# tx_no_transistor_adjustable_charging_cur.net
KiCad netlist of a schematic drawn in EAGLE
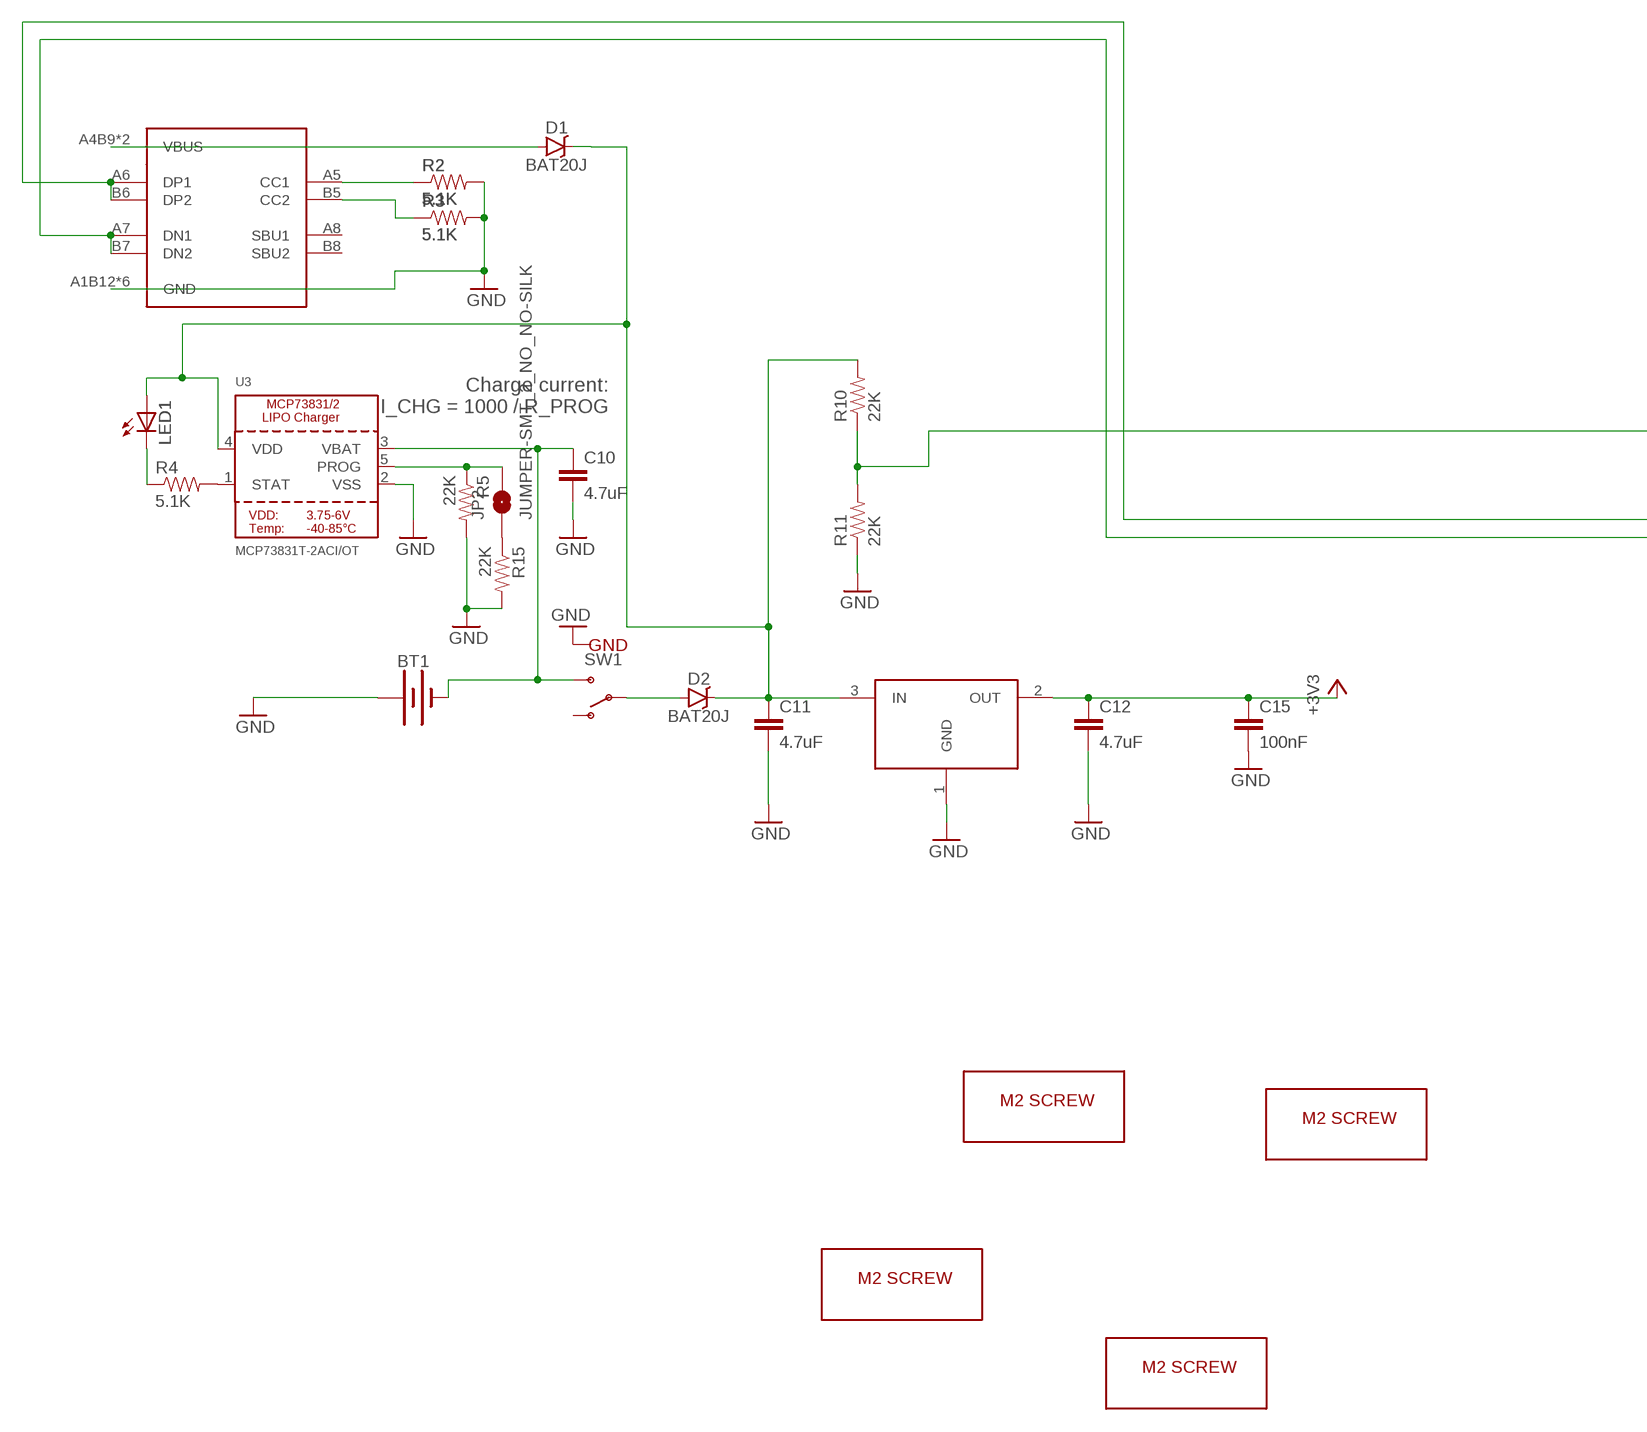
[diagram p0: schematic, sheet 1, part 1 of 2]
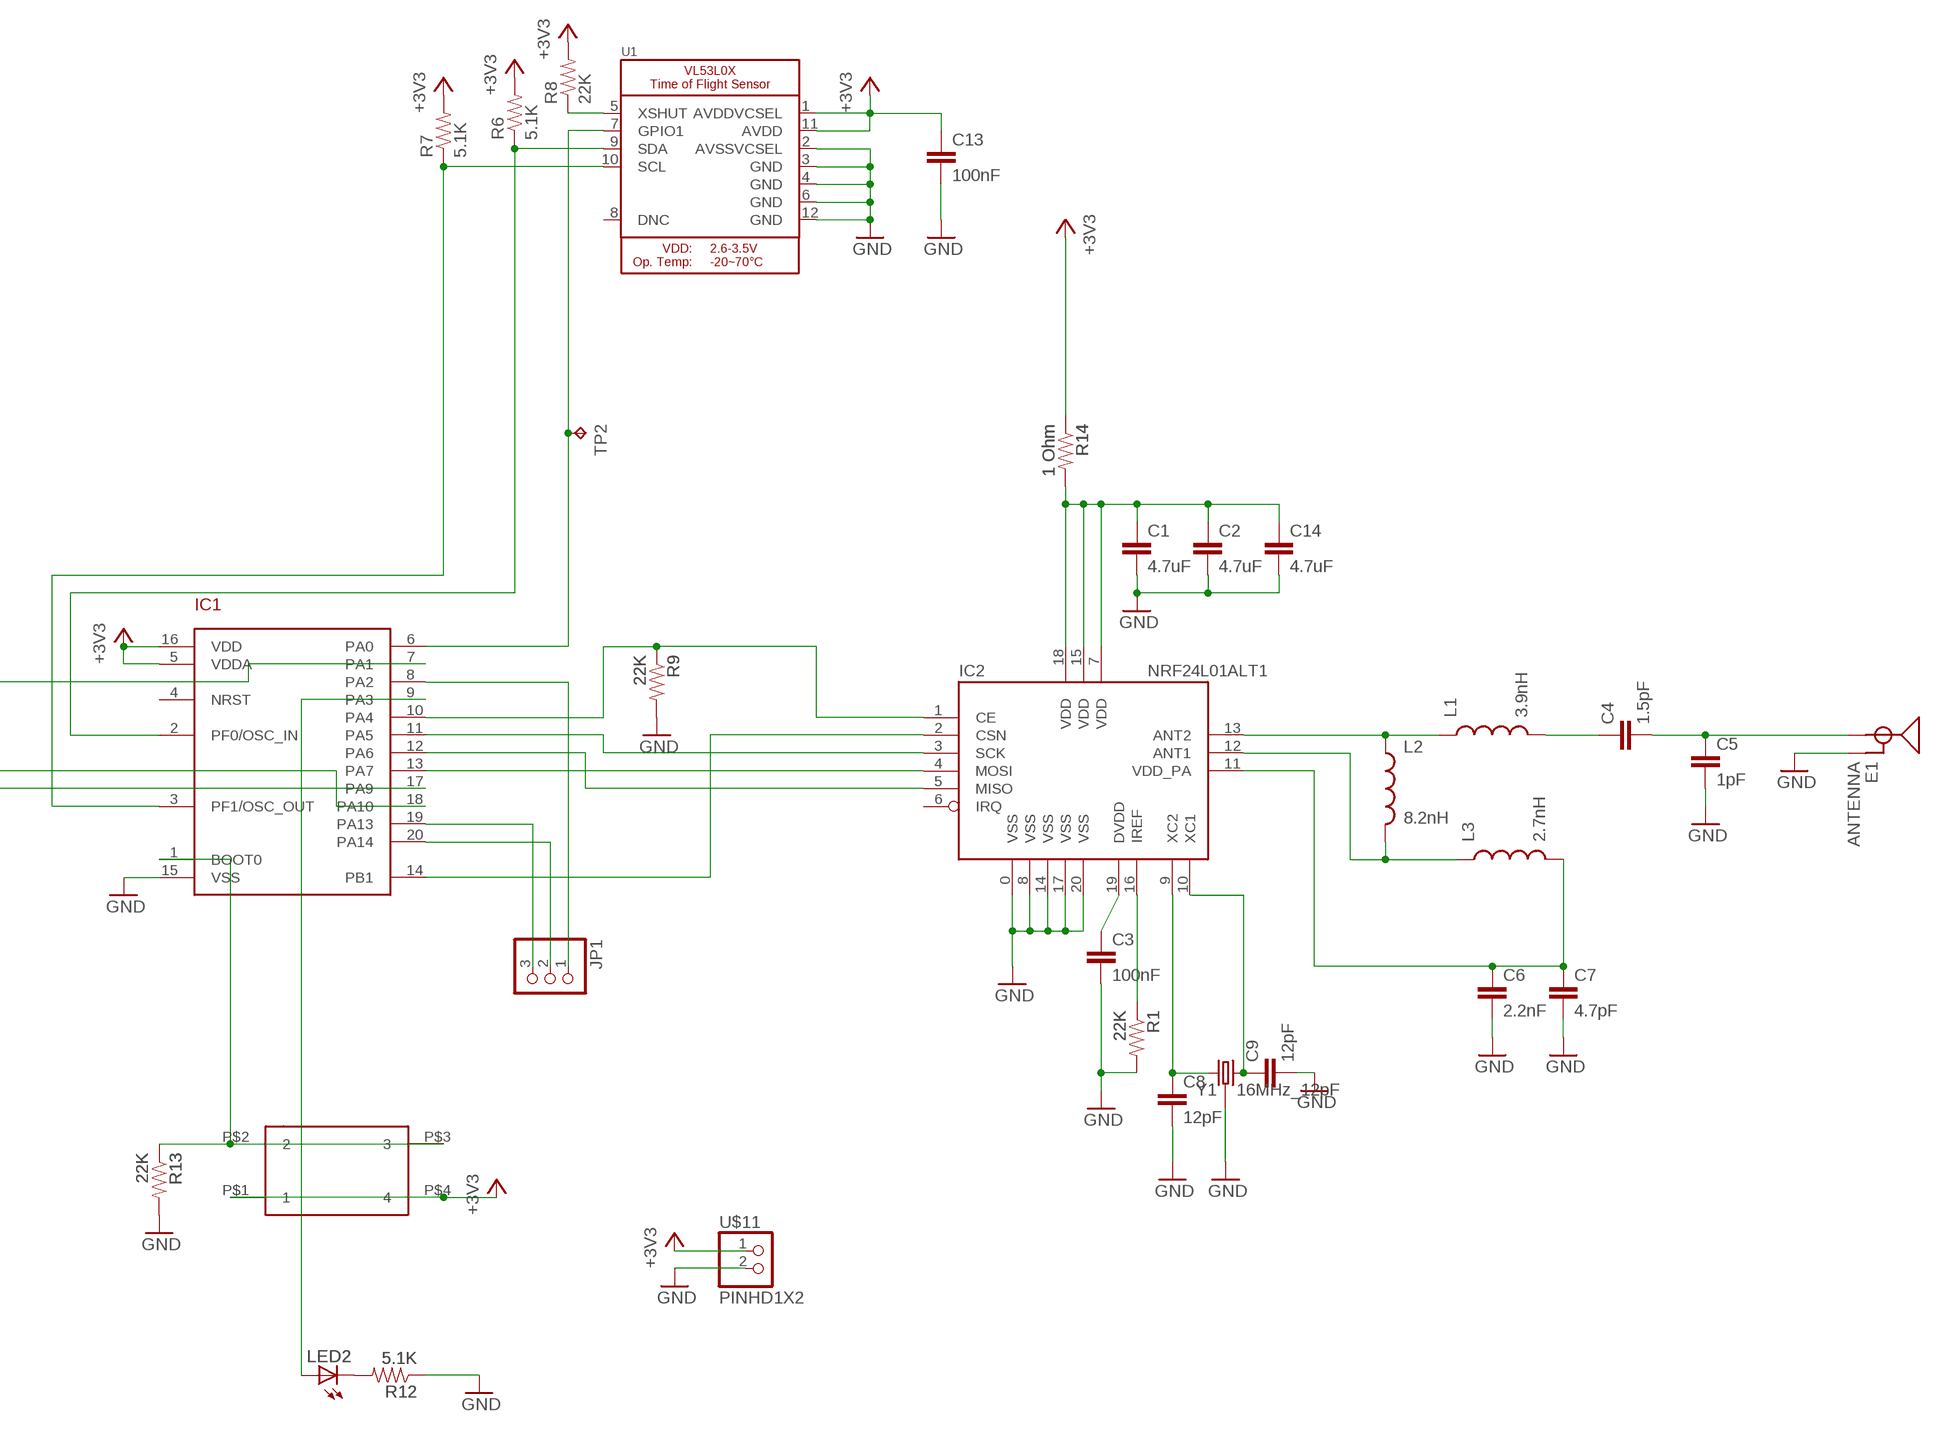
[diagram p1: schematic, sheet 1, part 2 of 2]

(export (version "E")
  (design (tool "Eeschema 10.0.6"))
  (components
    (comp (ref "BT1")
      (value "TX_SPARKFUN-BATTERIES_BATTERY-24.5MM_PTH")
      (footprint "eagle-import:TX_SPARKFUN-BATTERIES_BATTCON_24.5MM_PTH")
      (libsource (lib "eagle-import") (part "TX_SPARKFUN-BATTERIES_BATTERY-24.5MM_PTH"))
    )
    (comp (ref "C1")
      (value "4.7uF")
      (footprint "eagle-import:0805")
      (libsource (lib "eagle-import") (part "clock_CAP0805"))
    )
    (comp (ref "C2")
      (value "4.7uF")
      (footprint "eagle-import:0805")
      (libsource (lib "eagle-import") (part "clock_CAP0805"))
    )
    (comp (ref "C3")
      (value "100nF")
      (footprint "eagle-import:0805")
      (libsource (lib "eagle-import") (part "clock_CAP0805"))
    )
    (comp (ref "C4")
      (value "1.5pF")
      (footprint "eagle-import:0805")
      (libsource (lib "eagle-import") (part "clock_CAP0805"))
    )
    (comp (ref "C5")
      (value "1pF")
      (footprint "eagle-import:0805")
      (libsource (lib "eagle-import") (part "clock_CAP0805"))
    )
    (comp (ref "C6")
      (value "2.2nF")
      (footprint "eagle-import:0805")
      (libsource (lib "eagle-import") (part "clock_CAP0805"))
    )
    (comp (ref "C7")
      (value "4.7pF")
      (footprint "eagle-import:0805")
      (libsource (lib "eagle-import") (part "clock_CAP0805"))
    )
    (comp (ref "C8")
      (value "12pF")
      (footprint "eagle-import:0805")
      (libsource (lib "eagle-import") (part "clock_CAP0805"))
    )
    (comp (ref "C9")
      (value "12pF")
      (footprint "eagle-import:0805")
      (libsource (lib "eagle-import") (part "clock_CAP0805"))
    )
    (comp (ref "C10")
      (value "4.7uF")
      (footprint "eagle-import:0805")
      (libsource (lib "eagle-import") (part "CAP0805"))
    )
    (comp (ref "C11")
      (value "4.7uF")
      (footprint "eagle-import:0805")
      (libsource (lib "eagle-import") (part "clock_CAP0805"))
    )
    (comp (ref "C12")
      (value "4.7uF")
      (footprint "eagle-import:0805")
      (libsource (lib "eagle-import") (part "clock_CAP0805"))
    )
    (comp (ref "C13")
      (value "100nF")
      (footprint "eagle-import:0805")
      (libsource (lib "eagle-import") (part "clock_CAP0805"))
    )
    (comp (ref "C14")
      (value "4.7uF")
      (footprint "eagle-import:0805")
      (libsource (lib "eagle-import") (part "clock_CAP0805"))
    )
    (comp (ref "C15")
      (value "100nF")
      (footprint "eagle-import:0805")
      (libsource (lib "eagle-import") (part "clock_CAP0805"))
    )
    (comp (ref "D1")
      (value "BAT20J")
      (footprint "eagle-import:SOD-323")
      (libsource (lib "eagle-import") (part "DIODE-SCHOTTKY-BAT20J"))
    )
    (comp (ref "D2")
      (value "BAT20J")
      (footprint "eagle-import:SOD-323")
      (libsource (lib "eagle-import") (part "DIODE-SCHOTTKY-BAT20J"))
    )
    (comp (ref "E1")
      (value "ANTENNA")
      (footprint "eagle-import:TRACE_ANTENNA_2.4GHZ_25.7MM_TUNED")
      (libsource (lib "eagle-import") (part "ANTENNATRACE-TUNED"))
    )
    (comp (ref "IC1")
      (value "STM32F030F4")
      (footprint "eagle-import:TSSOP20")
      (libsource (lib "eagle-import") (part "STM32F030F4"))
    )
    (comp (ref "IC2")
      (value "NRF24L01ALT1")
      (footprint "eagle-import:QFN20_ALT1")
      (libsource (lib "eagle-import") (part "NRF24L01ALT1"))
    )
    (comp (ref "JP1")
      (value "PINHD-1X3CB")
      (footprint "eagle-import:1X03-CLEANBIG")
      (libsource (lib "eagle-import") (part "PINHD-1X3CB"))
    )
    (comp (ref "JP2")
      (value "JUMPER-SMT_2_NO_NO-SILK")
      (footprint "eagle-import:SMT-JUMPER_2_NO_NO-SILK")
      (libsource (lib "eagle-import") (part "JUMPER-SMT_2_NO_NO-SILK"))
    )
    (comp (ref "L1")
      (value "3.9nH")
      (footprint "eagle-import:0805")
      (libsource (lib "eagle-import") (part "INDUCTOR0805"))
    )
    (comp (ref "L2")
      (value "8.2nH")
      (footprint "eagle-import:0805")
      (libsource (lib "eagle-import") (part "INDUCTOR0805"))
    )
    (comp (ref "L3")
      (value "2.7nH")
      (footprint "eagle-import:0805")
      (libsource (lib "eagle-import") (part "INDUCTOR0805"))
    )
    (comp (ref "LED1")
      (value "LEDCHIP-LED0805")
      (footprint "eagle-import:CHIP-LED0805")
      (libsource (lib "eagle-import") (part "LEDCHIP-LED0805"))
    )
    (comp (ref "LED2")
      (value "LEDCHIP-LED0805")
      (footprint "eagle-import:CHIP-LED0805")
      (libsource (lib "eagle-import") (part "LEDCHIP-LED0805"))
    )
    (comp (ref "R1")
      (value "22K")
      (footprint "eagle-import:0805")
      (libsource (lib "eagle-import") (part "joyAnalog_RESISTOR0805-RES"))
    )
    (comp (ref "R2")
      (value "5.1K")
      (footprint "eagle-import:0805")
      (libsource (lib "eagle-import") (part "joyAnalog_RESISTOR0805-RES"))
    )
    (comp (ref "R3")
      (value "5.1K")
      (footprint "eagle-import:0805")
      (libsource (lib "eagle-import") (part "joyAnalog_RESISTOR0805-RES"))
    )
    (comp (ref "R4")
      (value "5.1K")
      (footprint "eagle-import:0805")
      (libsource (lib "eagle-import") (part "RESISTOR0805-RES"))
    )
    (comp (ref "R5")
      (value "22K")
      (footprint "eagle-import:0805")
      (libsource (lib "eagle-import") (part "RESISTOR0805-RES"))
    )
    (comp (ref "R6")
      (value "5.1K")
      (footprint "eagle-import:0805")
      (libsource (lib "eagle-import") (part "RESISTOR0805-RES"))
    )
    (comp (ref "R7")
      (value "5.1K")
      (footprint "eagle-import:0805")
      (libsource (lib "eagle-import") (part "RESISTOR0805-RES"))
    )
    (comp (ref "R8")
      (value "22K")
      (footprint "eagle-import:0805")
      (libsource (lib "eagle-import") (part "RESISTOR0805-RES"))
    )
    (comp (ref "R9")
      (value "22K")
      (footprint "eagle-import:0805")
      (libsource (lib "eagle-import") (part "joyAnalog_RESISTOR0805-RES"))
    )
    (comp (ref "R10")
      (value "22K")
      (footprint "eagle-import:0805")
      (libsource (lib "eagle-import") (part "RESISTOR0805-RES"))
    )
    (comp (ref "R11")
      (value "22K")
      (footprint "eagle-import:0805")
      (libsource (lib "eagle-import") (part "RESISTOR0805-RES"))
    )
    (comp (ref "R12")
      (value "5.1K")
      (footprint "eagle-import:0805")
      (libsource (lib "eagle-import") (part "joyAnalog_RESISTOR0805-RES"))
    )
    (comp (ref "R13")
      (value "22K")
      (footprint "eagle-import:0805")
      (libsource (lib "eagle-import") (part "joyAnalog_RESISTOR0805-RES"))
    )
    (comp (ref "R14")
      (value "1 Ohm")
      (footprint "eagle-import:0805")
      (libsource (lib "eagle-import") (part "joyAnalog_RESISTOR0805-RES"))
    )
    (comp (ref "R15")
      (value "22K")
      (footprint "eagle-import:0805")
      (libsource (lib "eagle-import") (part "RESISTOR0805-RES"))
    )
    (comp (ref "SW1")
      (value "SWITCH-SPDTTDFGDFG")
      (footprint "eagle-import:SWITCH-SPST-SMD-A")
      (libsource (lib "eagle-import") (part "SWITCH-SPDTTDFGDFG"))
    )
    (comp (ref "SW2")
      (value "324_SW324_SWITCH_FOOT_HOLE")
      (footprint "eagle-import:342_SWICH_FOOT_HOLE")
      (libsource (lib "eagle-import") (part "324_SW324_SWITCH_FOOT_HOLE"))
    )
    (comp (ref "TP2")
      (value "TPTP10R")
      (footprint "eagle-import:TP10R")
      (libsource (lib "eagle-import") (part "TPTP10R"))
    )
    (comp (ref "U$1")
      (value "M2_SCREW_DEV")
      (footprint "eagle-import:M2_SCREW_FOOT")
      (libsource (lib "eagle-import") (part "M2_SCREW_DEV"))
    )
    (comp (ref "U$11")
      (value "PINHD1X2")
      (footprint "eagle-import:1X02")
      (libsource (lib "eagle-import") (part "PINHD1X2"))
    )
    (comp (ref "U$12")
      (value "M2_SCREW_DEV")
      (footprint "eagle-import:M2_SCREW_FOOT")
      (libsource (lib "eagle-import") (part "M2_SCREW_DEV"))
    )
    (comp (ref "U$13")
      (value "M2_SCREW_DEV")
      (footprint "eagle-import:M2_SCREW_FOOT")
      (libsource (lib "eagle-import") (part "M2_SCREW_DEV"))
    )
    (comp (ref "U$14")
      (value "M2_SCREW_DEV")
      (footprint "eagle-import:M2_SCREW_FOOT")
      (libsource (lib "eagle-import") (part "M2_SCREW_DEV"))
    )
    (comp (ref "U1")
      (value "VL53L0X")
      (footprint "eagle-import:LGA12_ST")
      (libsource (lib "eagle-import") (part "VL53L0X"))
    )
    (comp (ref "U2")
      (value "USBC_16P")
      (footprint "eagle-import:USBC_16P_FOOT")
      (libsource (lib "eagle-import") (part "USBC_16P"))
    )
    (comp (ref "U3")
      (value "MCP73831T-2ACI/OT")
      (footprint "eagle-import:SOT23-5")
      (libsource (lib "eagle-import") (part "MCP73831/2"))
    )
    (comp (ref "U4")
      (value "XC6206_DEV")
      (footprint "eagle-import:SOT23R_INFINEON")
      (libsource (lib "eagle-import") (part "XC6206_DEV"))
    )
    (comp (ref "Y1")
      (value "16MHz_12pF")
      (footprint "eagle-import:CRYSTAL-SMD-3.2X2.5MM")
      (libsource (lib "eagle-import") (part "CRYSTAL-26MHZSMD-3.2X2.5"))
    )
  )
  (nets
    (net (code "1") (name "+3V3") (class "Default")
      (node (ref "C12") (pin "1") (pinfunction "1_1") (pintype "passive"))
      (node (ref "C13") (pin "1") (pinfunction "1_1") (pintype "passive"))
      (node (ref "C15") (pin "1") (pinfunction "1_1") (pintype "passive"))
      (node (ref "IC1") (pin "16") (pinfunction "VDD_16") (pintype "bidirectional"))
      (node (ref "IC1") (pin "5") (pinfunction "VDDA_5") (pintype "bidirectional"))
      (node (ref "R14") (pin "1") (pinfunction "1_1") (pintype "passive"))
      (node (ref "R6") (pin "2") (pinfunction "2_2") (pintype "passive"))
      (node (ref "R7") (pin "2") (pinfunction "2_2") (pintype "passive"))
      (node (ref "R8") (pin "2") (pinfunction "2_2") (pintype "passive"))
      (node (ref "SW2") (pin "P$1") (pinfunction "1_P$1") (pintype "bidirectional"))
      (node (ref "SW2") (pin "P$4") (pinfunction "4_P$4") (pintype "bidirectional"))
      (node (ref "U$11") (pin "1") (pinfunction "1_1") (pintype "passive"))
      (node (ref "U1") (pin "1") (pinfunction "AVDDVCSEL_1") (pintype "power_in"))
      (node (ref "U1") (pin "11") (pinfunction "AVDD_11") (pintype "power_in"))
      (node (ref "U4") (pin "2") (pinfunction "OUT_2") (pintype "bidirectional"))
    )
    (net (code "2") (name "GND") (class "Default")
      (node (ref "BT1") (pin "2") (pinfunction "+_2") (pintype "power_in"))
      (node (ref "C1") (pin "2") (pinfunction "2_2") (pintype "passive"))
      (node (ref "C10") (pin "2") (pinfunction "2_2") (pintype "passive"))
      (node (ref "C11") (pin "2") (pinfunction "2_2") (pintype "passive"))
      (node (ref "C12") (pin "2") (pinfunction "2_2") (pintype "passive"))
      (node (ref "C13") (pin "2") (pinfunction "2_2") (pintype "passive"))
      (node (ref "C14") (pin "2") (pinfunction "2_2") (pintype "passive"))
      (node (ref "C15") (pin "2") (pinfunction "2_2") (pintype "passive"))
      (node (ref "C2") (pin "2") (pinfunction "2_2") (pintype "passive"))
      (node (ref "C3") (pin "2") (pinfunction "2_2") (pintype "passive"))
      (node (ref "C5") (pin "2") (pinfunction "2_2") (pintype "passive"))
      (node (ref "C6") (pin "2") (pinfunction "2_2") (pintype "passive"))
      (node (ref "C7") (pin "2") (pinfunction "2_2") (pintype "passive"))
      (node (ref "C8") (pin "2") (pinfunction "2_2") (pintype "passive"))
      (node (ref "C9") (pin "2") (pinfunction "2_2") (pintype "passive"))
      (node (ref "E1") (pin "GND") (pinfunction "GND_GND") (pintype "bidirectional"))
      (node (ref "E1") (pin "GND2") (pinfunction "GND_GND2") (pintype "bidirectional"))
      (node (ref "IC1") (pin "15") (pinfunction "VSS_15") (pintype "bidirectional"))
      (node (ref "IC2") (pin "0") (pinfunction "VSS_0") (pintype "power_in"))
      (node (ref "IC2") (pin "14") (pinfunction "VSS_14") (pintype "power_in"))
      (node (ref "IC2") (pin "17") (pinfunction "VSS_17") (pintype "power_in"))
      (node (ref "IC2") (pin "20") (pinfunction "VSS_20") (pintype "power_in"))
      (node (ref "IC2") (pin "8") (pinfunction "VSS_8") (pintype "power_in"))
      (node (ref "R1") (pin "2") (pinfunction "2_2") (pintype "passive"))
      (node (ref "R11") (pin "1") (pinfunction "1_1") (pintype "passive"))
      (node (ref "R12") (pin "1") (pinfunction "1_1") (pintype "passive"))
      (node (ref "R13") (pin "2") (pinfunction "2_2") (pintype "passive"))
      (node (ref "R15") (pin "2") (pinfunction "2_2") (pintype "passive"))
      (node (ref "R2") (pin "2") (pinfunction "2_2") (pintype "passive"))
      (node (ref "R3") (pin "2") (pinfunction "2_2") (pintype "passive"))
      (node (ref "R5") (pin "2") (pinfunction "2_2") (pintype "passive"))
      (node (ref "R9") (pin "2") (pinfunction "2_2") (pintype "passive"))
      (node (ref "SW1") (pin "G1") (pinfunction "GND_G1") (pintype "passive"))
      (node (ref "SW1") (pin "G2") (pinfunction "GND_G2") (pintype "passive"))
      (node (ref "SW1") (pin "G3") (pinfunction "GND_G3") (pintype "passive"))
      (node (ref "SW1") (pin "G4") (pinfunction "GND_G4") (pintype "passive"))
      (node (ref "U$11") (pin "2") (pinfunction "2_2") (pintype "passive"))
      (node (ref "U1") (pin "12") (pinfunction "GND_12") (pintype "power_in"))
      (node (ref "U1") (pin "2") (pinfunction "AVSSVCSEL_2") (pintype "power_in"))
      (node (ref "U1") (pin "3") (pinfunction "GND_3") (pintype "power_in"))
      (node (ref "U1") (pin "4") (pinfunction "GND_4") (pintype "power_in"))
      (node (ref "U1") (pin "6") (pinfunction "GND_6") (pintype "power_in"))
      (node (ref "U2") (pin "A1B12") (pinfunction "GND_A1B12") (pintype "bidirectional"))
      (node (ref "U2") (pin "B11A12") (pinfunction "GND_B11A12") (pintype "bidirectional"))
      (node (ref "U2") (pin "P$13") (pinfunction "GND_P$13") (pintype "bidirectional"))
      (node (ref "U2") (pin "P$14") (pinfunction "GND_P$14") (pintype "bidirectional"))
      (node (ref "U2") (pin "P$15") (pinfunction "GND_P$15") (pintype "bidirectional"))
      (node (ref "U2") (pin "P$16") (pinfunction "GND_P$16") (pintype "bidirectional"))
      (node (ref "U3") (pin "2") (pinfunction "VSS_2") (pintype "power_in"))
      (node (ref "U4") (pin "1") (pinfunction "GND_1") (pintype "bidirectional"))
      (node (ref "Y1") (pin "2") (pinfunction "3_2") (pintype "passive"))
      (node (ref "Y1") (pin "4") (pinfunction "3_4") (pintype "passive"))
    )
    (net (code "3") (name "Net-(BT1--)") (class "Default")
      (node (ref "BT1") (pin "1") (pinfunction "-_1") (pintype "power_in"))
      (node (ref "C10") (pin "1") (pinfunction "1_1") (pintype "passive"))
      (node (ref "SW1") (pin "3") (pinfunction "S_3") (pintype "passive"))
      (node (ref "U3") (pin "3") (pinfunction "VBAT_3") (pintype "power_in"))
    )
    (net (code "4") (name "Net-(C1-Pad1)") (class "Default")
      (node (ref "C1") (pin "1") (pinfunction "1_1") (pintype "passive"))
      (node (ref "C14") (pin "1") (pinfunction "1_1") (pintype "passive"))
      (node (ref "C2") (pin "1") (pinfunction "1_1") (pintype "passive"))
      (node (ref "IC2") (pin "15") (pinfunction "VDD_15") (pintype "power_in"))
      (node (ref "IC2") (pin "18") (pinfunction "VDD_18") (pintype "power_in"))
      (node (ref "IC2") (pin "7") (pinfunction "VDD_7") (pintype "power_in"))
      (node (ref "R14") (pin "2") (pinfunction "2_2") (pintype "passive"))
    )
    (net (code "5") (name "Net-(C4-Pad1)") (class "Default")
      (node (ref "C4") (pin "1") (pinfunction "1_1") (pintype "passive"))
      (node (ref "L1") (pin "2") (pinfunction "2_2") (pintype "passive"))
    )
    (net (code "6") (name "Net-(D1-PadA)") (class "Default")
      (node (ref "D1") (pin "A") (pinfunction "A_A") (pintype "passive"))
      (node (ref "U2") (pin "A4B9") (pinfunction "VBUS_A4B9") (pintype "bidirectional"))
      (node (ref "U2") (pin "B4A9") (pinfunction "VBUS_B4A9") (pintype "bidirectional"))
    )
    (net (code "7") (name "Net-(E1-SIGNAL)") (class "Default")
      (node (ref "C4") (pin "2") (pinfunction "2_2") (pintype "passive"))
      (node (ref "C5") (pin "1") (pinfunction "1_1") (pintype "passive"))
      (node (ref "E1") (pin "ANT") (pinfunction "SIGNAL_ANT") (pintype "bidirectional"))
    )
    (net (code "8") (name "Net-(IC1-BOOT0)") (class "Default")
      (node (ref "IC1") (pin "1") (pinfunction "BOOT0_1") (pintype "bidirectional"))
      (node (ref "R13") (pin "1") (pinfunction "1_1") (pintype "passive"))
      (node (ref "SW2") (pin "P$2") (pinfunction "2_P$2") (pintype "bidirectional"))
      (node (ref "SW2") (pin "P$3") (pinfunction "3_P$3") (pintype "bidirectional"))
    )
    (net (code "9") (name "Net-(IC1-PA0)") (class "Default")
      (node (ref "IC1") (pin "6") (pinfunction "PA0_6") (pintype "bidirectional"))
      (node (ref "TP2") (pin "TP") (pinfunction "TP_TP") (pintype "input"))
      (node (ref "U1") (pin "7") (pinfunction "GPIO1_7") (pintype "output"))
    )
    (net (code "10") (name "Net-(IC1-PA1)") (class "Default")
      (node (ref "IC1") (pin "7") (pinfunction "PA1_7") (pintype "bidirectional"))
      (node (ref "R10") (pin "1") (pinfunction "1_1") (pintype "passive"))
      (node (ref "R11") (pin "2") (pinfunction "2_2") (pintype "passive"))
    )
    (net (code "11") (name "Net-(IC1-PA2)") (class "Default")
      (node (ref "IC1") (pin "8") (pinfunction "PA2_8") (pintype "bidirectional"))
      (node (ref "JP1") (pin "1") (pinfunction "1_1") (pintype "passive"))
    )
    (net (code "12") (name "Net-(IC1-PA3)") (class "Default")
      (node (ref "IC1") (pin "9") (pinfunction "PA3_9") (pintype "bidirectional"))
      (node (ref "LED2") (pin "A") (pinfunction "A_A") (pintype "passive"))
    )
    (net (code "13") (name "Net-(IC1-PA4)") (class "Default")
      (node (ref "IC1") (pin "10") (pinfunction "PA4_10") (pintype "bidirectional"))
      (node (ref "IC2") (pin "1") (pinfunction "CE_1") (pintype "input"))
      (node (ref "R9") (pin "1") (pinfunction "1_1") (pintype "passive"))
    )
    (net (code "14") (name "Net-(IC1-PA5)") (class "Default")
      (node (ref "IC1") (pin "11") (pinfunction "PA5_11") (pintype "bidirectional"))
      (node (ref "IC2") (pin "3") (pinfunction "SCK_3") (pintype "input"))
    )
    (net (code "15") (name "Net-(IC1-PA6)") (class "Default")
      (node (ref "IC1") (pin "12") (pinfunction "PA6_12") (pintype "bidirectional"))
      (node (ref "IC2") (pin "5") (pinfunction "MISO_5") (pintype "output"))
    )
    (net (code "16") (name "Net-(IC1-PA7)") (class "Default")
      (node (ref "IC1") (pin "13") (pinfunction "PA7_13") (pintype "bidirectional"))
      (node (ref "IC2") (pin "4") (pinfunction "MOSI_4") (pintype "input"))
    )
    (net (code "17") (name "Net-(IC1-PA9)") (class "Default")
      (node (ref "IC1") (pin "17") (pinfunction "PA9_17") (pintype "bidirectional"))
      (node (ref "U2") (pin "A7") (pinfunction "DN1_A7") (pintype "bidirectional"))
      (node (ref "U2") (pin "B7") (pinfunction "DN2_B7") (pintype "bidirectional"))
    )
    (net (code "18") (name "Net-(IC1-PA10)") (class "Default")
      (node (ref "IC1") (pin "18") (pinfunction "PA10_18") (pintype "bidirectional"))
      (node (ref "U2") (pin "A6") (pinfunction "DP1_A6") (pintype "bidirectional"))
      (node (ref "U2") (pin "B6") (pinfunction "DP2_B6") (pintype "bidirectional"))
    )
    (net (code "19") (name "Net-(IC1-PA13)") (class "Default")
      (node (ref "IC1") (pin "19") (pinfunction "PA13_19") (pintype "bidirectional"))
      (node (ref "JP1") (pin "3") (pinfunction "3_3") (pintype "passive"))
    )
    (net (code "20") (name "Net-(IC1-PA14)") (class "Default")
      (node (ref "IC1") (pin "20") (pinfunction "PA14_20") (pintype "bidirectional"))
      (node (ref "JP1") (pin "2") (pinfunction "2_2") (pintype "passive"))
    )
    (net (code "21") (name "Net-(IC1-PB1)") (class "Default")
      (node (ref "IC1") (pin "14") (pinfunction "PB1_14") (pintype "bidirectional"))
      (node (ref "IC2") (pin "2") (pinfunction "CSN_2") (pintype "input"))
    )
    (net (code "22") (name "Net-(IC1-PF0{slash}OSC_IN)") (class "Default")
      (node (ref "IC1") (pin "2") (pinfunction "PF0/OSC_IN_2") (pintype "bidirectional"))
      (node (ref "R6") (pin "1") (pinfunction "1_1") (pintype "passive"))
      (node (ref "U1") (pin "9") (pinfunction "SDA_9") (pintype "open_collector"))
    )
    (net (code "23") (name "Net-(IC1-PF1{slash}OSC_OUT)") (class "Default")
      (node (ref "IC1") (pin "3") (pinfunction "PF1/OSC_OUT_3") (pintype "bidirectional"))
      (node (ref "R7") (pin "1") (pinfunction "1_1") (pintype "passive"))
      (node (ref "U1") (pin "10") (pinfunction "SCL_10") (pintype "open_collector"))
    )
    (net (code "24") (name "Net-(IC2-ANT1)") (class "Default")
      (node (ref "IC2") (pin "12") (pinfunction "ANT1_12") (pintype "output"))
      (node (ref "L2") (pin "2") (pinfunction "2_2") (pintype "passive"))
      (node (ref "L3") (pin "1") (pinfunction "1_1") (pintype "passive"))
    )
    (net (code "25") (name "Net-(IC2-ANT2)") (class "Default")
      (node (ref "IC2") (pin "13") (pinfunction "ANT2_13") (pintype "output"))
      (node (ref "L1") (pin "1") (pinfunction "1_1") (pintype "passive"))
      (node (ref "L2") (pin "1") (pinfunction "1_1") (pintype "passive"))
    )
    (net (code "26") (name "Net-(IC2-DVDD)") (class "Default")
      (node (ref "C3") (pin "1") (pinfunction "1_1") (pintype "passive"))
      (node (ref "IC2") (pin "19") (pinfunction "DVDD_19") (pintype "power_in"))
    )
    (net (code "27") (name "Net-(IC2-IREF)") (class "Default")
      (node (ref "IC2") (pin "16") (pinfunction "IREF_16") (pintype "input"))
      (node (ref "R1") (pin "1") (pinfunction "1_1") (pintype "passive"))
    )
    (net (code "28") (name "Net-(IC2-VDD_PA)") (class "Default")
      (node (ref "C6") (pin "1") (pinfunction "1_1") (pintype "passive"))
      (node (ref "C7") (pin "1") (pinfunction "1_1") (pintype "passive"))
      (node (ref "IC2") (pin "11") (pinfunction "VDD_PA_11") (pintype "power_in"))
      (node (ref "L3") (pin "2") (pinfunction "2_2") (pintype "passive"))
    )
    (net (code "29") (name "Net-(IC2-XC1)") (class "Default")
      (node (ref "C9") (pin "1") (pinfunction "1_1") (pintype "passive"))
      (node (ref "IC2") (pin "10") (pinfunction "XC1_10") (pintype "input"))
      (node (ref "Y1") (pin "3") (pinfunction "2_3") (pintype "passive"))
    )
    (net (code "30") (name "Net-(IC2-XC2)") (class "Default")
      (node (ref "C8") (pin "1") (pinfunction "1_1") (pintype "passive"))
      (node (ref "IC2") (pin "9") (pinfunction "XC2_9") (pintype "input"))
      (node (ref "Y1") (pin "1") (pinfunction "1_1") (pintype "passive"))
    )
    (net (code "31") (name "Net-(JP2-Pad1)") (class "Default")
      (node (ref "JP2") (pin "1") (pinfunction "1_1") (pintype "passive"))
      (node (ref "R15") (pin "1") (pinfunction "1_1") (pintype "passive"))
    )
    (net (code "32") (name "Net-(LED1-PadC)") (class "Default")
      (node (ref "LED1") (pin "C") (pinfunction "C_C") (pintype "passive"))
      (node (ref "R4") (pin "1") (pinfunction "1_1") (pintype "passive"))
    )
    (net (code "33") (name "Net-(LED2-PadC)") (class "Default")
      (node (ref "LED2") (pin "C") (pinfunction "C_C") (pintype "passive"))
      (node (ref "R12") (pin "2") (pinfunction "2_2") (pintype "passive"))
    )
    (net (code "34") (name "Net-(SW1-P)") (class "Default")
      (node (ref "D2") (pin "A") (pinfunction "A_A") (pintype "passive"))
      (node (ref "SW1") (pin "2") (pinfunction "P_2") (pintype "passive"))
    )
    (net (code "35") (name "Net-(U1-XSHUT)") (class "Default")
      (node (ref "R8") (pin "1") (pinfunction "1_1") (pintype "passive"))
      (node (ref "U1") (pin "5") (pinfunction "XSHUT_5") (pintype "input"))
    )
    (net (code "36") (name "Net-(U2-CC1)") (class "Default")
      (node (ref "R2") (pin "1") (pinfunction "1_1") (pintype "passive"))
      (node (ref "U2") (pin "A5") (pinfunction "CC1_A5") (pintype "bidirectional"))
    )
    (net (code "37") (name "Net-(U2-CC2)") (class "Default")
      (node (ref "R3") (pin "1") (pinfunction "1_1") (pintype "passive"))
      (node (ref "U2") (pin "B5") (pinfunction "CC2_B5") (pintype "bidirectional"))
    )
    (net (code "38") (name "Net-(U3-PROG)") (class "Default")
      (node (ref "JP2") (pin "2") (pinfunction "2_2") (pintype "passive"))
      (node (ref "R5") (pin "1") (pinfunction "1_1") (pintype "passive"))
      (node (ref "U3") (pin "5") (pinfunction "PROG_5") (pintype "input"))
    )
    (net (code "39") (name "Net-(U3-STAT)") (class "Default")
      (node (ref "R4") (pin "2") (pinfunction "2_2") (pintype "passive"))
      (node (ref "U3") (pin "1") (pinfunction "STAT_1") (pintype "output"))
    )
    (net (code "40") (name "Net-(U3-VDD)") (class "Default")
      (node (ref "C11") (pin "1") (pinfunction "1_1") (pintype "passive"))
      (node (ref "D1") (pin "C") (pinfunction "C_C") (pintype "passive"))
      (node (ref "D2") (pin "C") (pinfunction "C_C") (pintype "passive"))
      (node (ref "LED1") (pin "A") (pinfunction "A_A") (pintype "passive"))
      (node (ref "R10") (pin "2") (pinfunction "2_2") (pintype "passive"))
      (node (ref "U3") (pin "4") (pinfunction "VDD_4") (pintype "power_in"))
      (node (ref "U4") (pin "3") (pinfunction "IN_3") (pintype "bidirectional"))
    )
    (net (code "41") (name "unconnected-(IC1-NRST-Pad4)") (class "Default")
      (node (ref "IC1") (pin "4") (pinfunction "NRST_4") (pintype "bidirectional"))
    )
    (net (code "42") (name "unconnected-(IC2-IRQ-Pad6)") (class "Default")
      (node (ref "IC2") (pin "6") (pinfunction "IRQ_6") (pintype "output"))
    )
    (net (code "43") (name "unconnected-(SW1-O-Pad1)") (class "Default")
      (node (ref "SW1") (pin "1") (pinfunction "O_1") (pintype "passive"))
    )
    (net (code "44") (name "unconnected-(U1-DNC-Pad8)") (class "Default")
      (node (ref "U1") (pin "8") (pinfunction "DNC_8") (pintype "no_connect"))
    )
    (net (code "45") (name "unconnected-(U2-SBU1-PadA8)") (class "Default")
      (node (ref "U2") (pin "A8") (pinfunction "SBU1_A8") (pintype "bidirectional"))
    )
    (net (code "46") (name "unconnected-(U2-SBU2-PadB8)") (class "Default")
      (node (ref "U2") (pin "B8") (pinfunction "SBU2_B8") (pintype "bidirectional"))
    )
  )
)
